# driver.net
KiCad netlist of a schematic drawn in Altium Designer
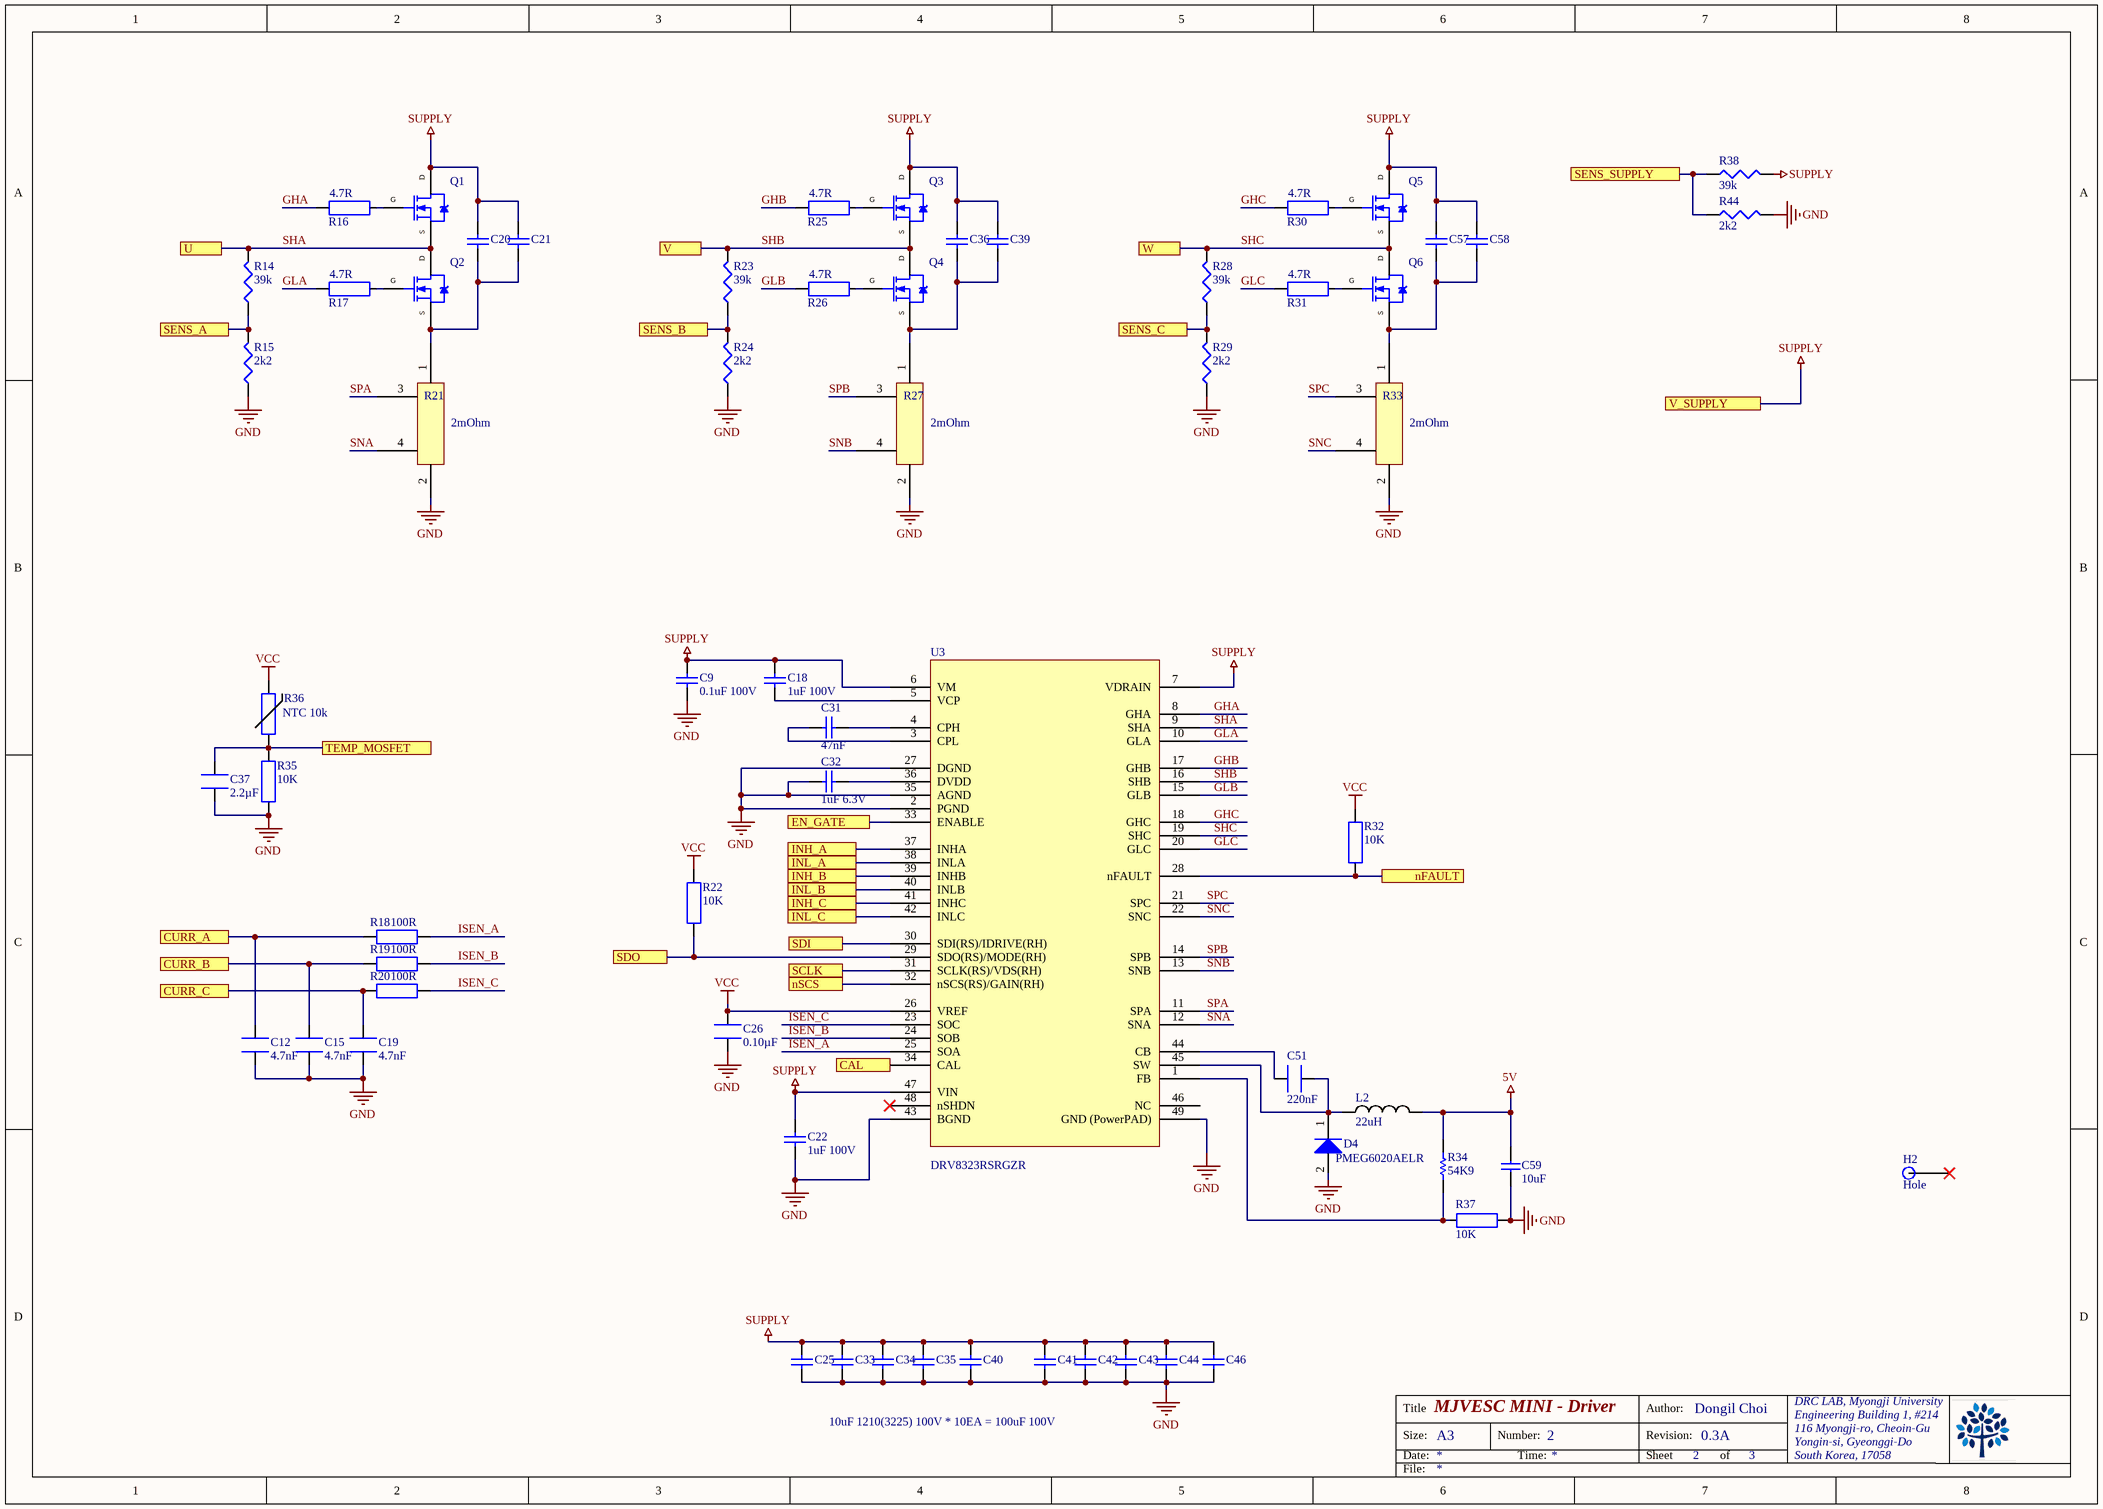
[diagram p0: driver.SchDoc]

(export (version "E")
  (design (tool "Eeschema 10.0.6"))
  (components
    (comp (ref "C9")
      (value "0.1uF 100V")
      (footprint "CAP 0603/1608")
      (description "Multilayer Ceramic Capacitors MLCC - SMD/SMT 0603 0.1uF 100volts X7R 10%")
      (fields (field (name "MANUFACTURER") "Murata") (field (name "PARTNUMBER") "GCJ188R72A104KA01D"))
      (libsource (lib "Altium_CDI_Library_Combined") (part "CAP"))
    )
    (comp (ref "C12")
      (value "4.7nF")
      (footprint "CAP 0603/1608")
      (description "CAP CER 4.7nF 50V NP0 0603")
      (fields (field (name "PARTNUMBER") "GRM1887U1H472JA01D"))
      (libsource (lib "CustomComponents") (part "GRM1885C1H222JA01D"))
    )
    (comp (ref "C15")
      (value "4.7nF")
      (footprint "CAP 0603/1608")
      (description "CAP CER 4.7nF 50V NP0 0603")
      (fields (field (name "PARTNUMBER") "GRM1887U1H472JA01D"))
      (libsource (lib "CustomComponents") (part "GRM1885C1H222JA01D"))
    )
    (comp (ref "C18")
      (value "1uF 100V")
      (footprint "C0805")
      (description "Multilayer Ceramic Capacitors MLCC - SMD/SMT 1.0UF 100V 10% 0805")
      (fields (field (name "MANUFACTURER") "Murata") (field (name "PARTNUMBER") "GRM21BC72A105KE01L"))
      (libsource (lib "Altium_CDI_Library_Combined") (part "CAP"))
    )
    (comp (ref "C19")
      (value "4.7nF")
      (footprint "CAP 0603/1608")
      (description "CAP CER 4.7nF 50V NP0 0603")
      (fields (field (name "PARTNUMBER") "GRM1887U1H472JA01D"))
      (libsource (lib "CustomComponents") (part "GRM1885C1H222JA01D"))
    )
    (comp (ref "C20")
      (value "CAP 10uF 100V 1210(3225)")
      (footprint "CAPC1210(3225)280_N")
      (description "100Vdc 10uF 10% 1210/2502")
      (fields (field (name "TOLERANCE") "Â±20%") (field (name "PARTNUMBER") "GRM32EC72A106KE05L"))
      (libsource (lib "Altium Content Vault") (part "CAP"))
    )
    (comp (ref "C21")
      (value "CAP 10uF 100V 1210(3225)")
      (footprint "CAPC1210(3225)280_N")
      (description "100Vdc 10uF 10% 1210/2502")
      (fields (field (name "TOLERANCE") "Â±20%") (field (name "PARTNUMBER") "GRM32EC72A106KE05L"))
      (libsource (lib "Altium Content Vault") (part "CAP"))
    )
    (comp (ref "C22")
      (value "1uF 100V")
      (footprint "C0805")
      (description "Multilayer Ceramic Capacitors MLCC - SMD/SMT 1.0UF 100V 10% 0805")
      (fields (field (name "MANUFACTURER") "Murata") (field (name "PART NUMBER") "GRM21BC72A105KE01L"))
      (libsource (lib "Altium_CDI_Library_Combined") (part "CAP"))
    )
    (comp (ref "C25")
      (value "CAP 10uF 100V 1210(3225)")
      (footprint "CAPC1210(3225)280_N")
      (description "100Vdc 10uF 10% 1210/2502")
      (fields (field (name "TOLERANCE") "Â±20%") (field (name "PARTNUMBER") "GRM32EC72A106KE05L"))
      (libsource (lib "Altium Content Vault") (part "CAP"))
    )
    (comp (ref "C26")
      (value "0.10µF")
      (footprint "CAP 0603/1608")
      (description "CAP CER 0.1UF 25V X7R 0603")
      (fields
        (field (name "MANUFACTURER") "Murata Electronics North America")
        (field (name "MANUFACTURER PART NUMBER") "GRM188R71E104KA01D")
      )
      (libsource (lib "CustomComponents") (part "GRM188R71E104KA01D"))
    )
    (comp (ref "C31")
      (value "47nF")
      (footprint "CAPC0603(1608)100_L")
      (description "CAP 47nF 16V ±5% 0603 (1608 Metric) Thickness 1mm SMD")
      (fields (field (name "TOLERANCE") "Â±10%") (field (name "PARTNUMBER") "CC0603KRX7R7BB473"))
      (libsource (lib "Altium Content Vault") (part "CAP"))
    )
    (comp (ref "C32")
      (value "1uF 6.3V")
      (footprint "CAPC0603(1608)100_N")
      (description "CAP 1uF 6.3V ±10% 0603 (1608 Metric) Thickness 1mm SMD")
      (fields (field (name "TOLERANCE") "Â±10%") (field (name "PARTNUMBER") "CC0603KRX7R5BB105"))
      (libsource (lib "Altium Content Vault") (part "CAP"))
    )
    (comp (ref "C33")
      (value "CAP 10uF 100V 1210(3225)")
      (footprint "CAPC1210(3225)280_N")
      (description "100Vdc 10uF 10% 1210/2502")
      (fields (field (name "TOLERANCE") "Â±20%") (field (name "PARTNUMBER") "GRM32EC72A106KE05L"))
      (libsource (lib "Altium Content Vault") (part "CAP"))
    )
    (comp (ref "C34")
      (value "CAP 10uF 100V 1210(3225)")
      (footprint "CAPC1210(3225)280_N")
      (description "100Vdc 10uF 10% 1210/2502")
      (fields (field (name "TOLERANCE") "Â±20%") (field (name "PARTNUMBER") "GRM32EC72A106KE05L"))
      (libsource (lib "Altium Content Vault") (part "CAP"))
    )
    (comp (ref "C35")
      (value "CAP 10uF 100V 1210(3225)")
      (footprint "CAPC1210(3225)280_N")
      (description "100Vdc 10uF 10% 1210/2502")
      (fields (field (name "TOLERANCE") "Â±20%") (field (name "PARTNUMBER") "GRM32EC72A106KE05L"))
      (libsource (lib "Altium Content Vault") (part "CAP"))
    )
    (comp (ref "C36")
      (value "CAP 10uF 100V 1210(3225)")
      (footprint "CAPC1210(3225)280_N")
      (description "100Vdc 10uF 10% 1210/2502")
      (fields (field (name "TOLERANCE") "Â±20%") (field (name "PARTNUMBER") "GRM32EC72A106KE05L"))
      (libsource (lib "Altium Content Vault") (part "CAP"))
    )
    (comp (ref "C37")
      (value "2.2µF")
      (footprint "CAP 0603/1608")
      (description "CAP CER 2.2UF 16V X5R 0603")
      (fields
        (field (name "MANUFACTURER") "Murata Electronics North America")
        (field (name "MANUFACTURER PART NUMBER") "GRM188R61C225KE15D")
      )
      (libsource (lib "CustomComponents") (part "GRM188R61C225KE15D"))
    )
    (comp (ref "C39")
      (value "CAP 10uF 100V 1210(3225)")
      (footprint "CAPC1210(3225)280_N")
      (description "100Vdc 10uF 10% 1210/2502")
      (fields (field (name "TOLERANCE") "Â±20%") (field (name "PARTNUMBER") "GRM32EC72A106KE05L"))
      (libsource (lib "Altium Content Vault") (part "CAP"))
    )
    (comp (ref "C40")
      (value "CAP 10uF 100V 1210(3225)")
      (footprint "CAPC1210(3225)280_N")
      (description "100Vdc 10uF 10% 1210/2502")
      (fields (field (name "TOLERANCE") "Â±20%") (field (name "PARTNUMBER") "GRM32EC72A106KE05L"))
      (libsource (lib "Altium Content Vault") (part "CAP"))
    )
    (comp (ref "C41")
      (value "CAP 10uF 100V 1210(3225)")
      (footprint "CAPC1210(3225)280_N")
      (description "100Vdc 10uF 10% 1210/2502")
      (fields (field (name "TOLERANCE") "Â±20%") (field (name "PARTNUMBER") "GRM32EC72A106KE05L"))
      (libsource (lib "Altium Content Vault") (part "CAP"))
    )
    (comp (ref "C42")
      (value "CAP 10uF 100V 1210(3225)")
      (footprint "CAPC1210(3225)280_N")
      (description "100Vdc 10uF 10% 1210/2502")
      (fields (field (name "TOLERANCE") "Â±20%") (field (name "PARTNUMBER") "GRM32EC72A106KE05L"))
      (libsource (lib "Altium Content Vault") (part "CAP"))
    )
    (comp (ref "C43")
      (value "CAP 10uF 100V 1210(3225)")
      (footprint "CAPC1210(3225)280_N")
      (description "100Vdc 10uF 10% 1210/2502")
      (fields (field (name "TOLERANCE") "Â±20%") (field (name "PARTNUMBER") "GRM32EC72A106KE05L"))
      (libsource (lib "Altium Content Vault") (part "CAP"))
    )
    (comp (ref "C44")
      (value "CAP 10uF 100V 1210(3225)")
      (footprint "CAPC1210(3225)280_N")
      (description "100Vdc 10uF 10% 1210/2502")
      (fields (field (name "TOLERANCE") "Â±20%") (field (name "PARTNUMBER") "GRM32EC72A106KE05L"))
      (libsource (lib "Altium Content Vault") (part "CAP"))
    )
    (comp (ref "C46")
      (value "CAP 10uF 100V 1210(3225)")
      (footprint "CAPC1210(3225)280_N")
      (description "100Vdc 10uF 10% 1210/2502")
      (fields (field (name "TOLERANCE") "Â±20%") (field (name "PARTNUMBER") "GRM32EC72A106KE05L"))
      (libsource (lib "Altium Content Vault") (part "CAP"))
    )
    (comp (ref "C51")
      (value "220nF")
      (footprint "CAP 0603/1608")
      (description "CAP CER 220nF 50V X7R 0603")
      (fields (field (name "PARTNUMBER") "GRM188R71H224KAC4J"))
      (libsource (lib "CustomComponents") (part "GRM188R71E104KA01D"))
    )
    (comp (ref "C57")
      (value "CAP 10uF 100V 1210(3225)")
      (footprint "CAPC1210(3225)280_N")
      (description "100Vdc 10uF 10% 1210/2502")
      (fields (field (name "TOLERANCE") "Â±20%") (field (name "PARTNUMBER") "GRM32EC72A106KE05L"))
      (libsource (lib "Altium Content Vault") (part "CAP"))
    )
    (comp (ref "C58")
      (value "CAP 10uF 100V 1210(3225)")
      (footprint "CAPC1210(3225)280_N")
      (description "100Vdc 10uF 10% 1210/2502")
      (fields (field (name "TOLERANCE") "Â±20%") (field (name "PARTNUMBER") "GRM32EC72A106KE05L"))
      (libsource (lib "Altium Content Vault") (part "CAP"))
    )
    (comp (ref "C59")
      (value "10uF")
      (footprint "CAPC1206(3216)190_M")
      (description "Multilayer Ceramic Capacitors MLCC - SMD/SMT 16V 10uF 10% 1.60mm X8L AEC-Q200")
      (fields (field (name "PARTNUMBER") "CGA5L1X8L1C106K160AC"))
      (libsource (lib "Altium_CDI_Library_Combined") (part "CGA5L1X8L1C106K160AC"))
    )
    (comp (ref "D4")
      (value "PMEG6020AELR")
      (footprint "SOD123W")
      (description "60 V, 2 A low leakage current Schottky barrier rectifier")
      (libsource (lib "Altium_CDI_Library_Combined") (part "PMEG6020AELR"))
    )
    (comp (ref "H2")
      (value "Hole")
      (footprint "M2-HOLE")
      (description "M2, M2.5, M3 Hole")
      (libsource (lib "Altium_CDI_Library_Combined") (part "Hole"))
    )
    (comp (ref "L2")
      (value "22uH")
      (footprint "74438335220")
      (description "Fixed Inductors WE-MAPI SMD 3015 22uH 0.60A 1040mOhm")
      (fields (field (name "PARTNUMBER") "74438335220"))
      (libsource (lib "Altium_CDI_Library_Combined") (part "74438335220"))
    )
    (comp (ref "Q1")
      (value "NTMFS5C604NLT1G")
      (footprint "DFN500X600X110-5N")
      (description "Power MOSFET\r\n60 V, 1.2 m, 287 A, Single N−Channel")
      (fields (field (name "MANUFACTURER") "International Rectifier"))
      (libsource (lib "Altium_CDI_Library_Combined") (part "NTMFS5C604NLT1G"))
    )
    (comp (ref "Q2")
      (value "NTMFS5C604NLT1G")
      (footprint "DFN500X600X110-5N")
      (description "Power MOSFET\r\n60 V, 1.2 m, 287 A, Single N−Channel")
      (fields (field (name "MANUFACTURER") "International Rectifier"))
      (libsource (lib "Altium_CDI_Library_Combined") (part "NTMFS5C604NLT1G"))
    )
    (comp (ref "Q3")
      (value "NTMFS5C604NLT1G")
      (footprint "DFN500X600X110-5N")
      (description "Power MOSFET\r\n60 V, 1.2 m, 287 A, Single N−Channel")
      (fields (field (name "MANUFACTURER") "International Rectifier"))
      (libsource (lib "Altium_CDI_Library_Combined") (part "NTMFS5C604NLT1G"))
    )
    (comp (ref "Q4")
      (value "NTMFS5C604NLT1G")
      (footprint "DFN500X600X110-5N")
      (description "Power MOSFET\r\n60 V, 1.2 m, 287 A, Single N−Channel")
      (fields (field (name "MANUFACTURER") "International Rectifier"))
      (libsource (lib "Altium_CDI_Library_Combined") (part "NTMFS5C604NLT1G"))
    )
    (comp (ref "Q5")
      (value "NTMFS5C604NLT1G")
      (footprint "DFN500X600X110-5N")
      (description "Power MOSFET\r\n60 V, 1.2 m, 287 A, Single N−Channel")
      (fields (field (name "MANUFACTURER") "International Rectifier"))
      (libsource (lib "Altium_CDI_Library_Combined") (part "NTMFS5C604NLT1G"))
    )
    (comp (ref "Q6")
      (value "NTMFS5C604NLT1G")
      (footprint "DFN500X600X110-5N")
      (description "Power MOSFET\r\n60 V, 1.2 m, 287 A, Single N−Channel")
      (fields (field (name "MANUFACTURER") "International Rectifier"))
      (libsource (lib "Altium_CDI_Library_Combined") (part "NTMFS5C604NLT1G"))
    )
    (comp (ref "R14")
      (value "39k")
      (footprint "RES 0603/1608")
      (description "RES SMD 39K OHM 1% 1/10W 0603")
      (fields (field (name "PARTNUMBER") "RC0603FR-0739KL") (field (name "PUBLISHER") "Altium Limited"))
      (libsource (lib "Miscellaneous Devices") (part "Res3"))
    )
    (comp (ref "R15")
      (value "2k2")
      (footprint "RES 0603/1608")
      (description "RES SMD 2.2K OHM 1% 1/10W 0603")
      (fields (field (name "PARTNUMBER") "RC0603FR-072K2L") (field (name "PUBLISHER") "Altium Limited"))
      (libsource (lib "Miscellaneous Devices") (part "Res3"))
    )
    (comp (ref "R16")
      (value "4.7R")
      (footprint "RES 0603/1608")
      (description "4.7R 0.1W 1% 0603 (1608 Metric)  SMD")
      (fields (field (name "PARTNUMBER") "RC0603FR-074R7L"))
      (libsource (lib "Altium_CDI_Library_Combined") (part "RC0603FR-072RL"))
    )
    (comp (ref "R17")
      (value "4.7R")
      (footprint "RES 0603/1608")
      (description "4.7R 0.1W 1% 0603 (1608 Metric)  SMD")
      (fields (field (name "PARTNUMBER") "RC0603FR-074R7L"))
      (libsource (lib "Altium_CDI_Library_Combined") (part "RC0603FR-072RL"))
    )
    (comp (ref "R18")
      (value "100R")
      (footprint "RES 0603/1608")
      (description "RES SMD 100R OHM 1% 1/10W 0603")
      (fields (field (name "PARTNUMBER") "RC0603JR-07100RL"))
      (libsource (lib "CustomComponents") (part "RC0603FR-07120RL"))
    )
    (comp (ref "R19")
      (value "100R")
      (footprint "RES 0603/1608")
      (description "RES SMD 100R OHM 1% 1/10W 0603")
      (fields (field (name "PARTNUMBER") "RC0603JR-07100RL"))
      (libsource (lib "CustomComponents") (part "RC0603FR-07120RL"))
    )
    (comp (ref "R20")
      (value "100R")
      (footprint "RES 0603/1608")
      (description "RES SMD 100R OHM 1% 1/10W 0603")
      (fields (field (name "PARTNUMBER") "RC0603JR-07100RL"))
      (libsource (lib "CustomComponents") (part "RC0603FR-07120RL"))
    )
    (comp (ref "R21")
      (value "2mOhm")
      (footprint "CSS2H-2512K-2L00F")
      (description "Current Sense Resistors - SMD 2mOhms 5W 1% AEC-Q200")
      (fields (field (name "PARTNUMBER") "CSS2H-2512K-2L00F"))
      (libsource (lib "Altium_CDI_Library_Combined") (part "CSS2H-2512K-2L00F"))
    )
    (comp (ref "R22")
      (value "10K")
      (footprint "RES 0603/1608")
      (description "RES SMD 10K OHM 1% 1/10W 0603")
      (fields
        (field (name "MANUFACTURER") "Yageo")
        (field (name "MANUFACTURER PART NUMBER") "RC0603FR-0710KL")
      )
      (libsource (lib "CustomComponents") (part "RC0603FR-0710KL"))
    )
    (comp (ref "R23")
      (value "39k")
      (footprint "RES 0603/1608")
      (description "RES SMD 39K OHM 1% 1/10W 0603")
      (fields (field (name "PARTNUMBER") "RC0603FR-0739KL") (field (name "PUBLISHER") "Altium Limited"))
      (libsource (lib "Miscellaneous Devices") (part "Res3"))
    )
    (comp (ref "R24")
      (value "2k2")
      (footprint "RES 0603/1608")
      (description "RES SMD 2.2K OHM 1% 1/10W 0603")
      (fields (field (name "PARTNUMBER") "RC0603FR-072K2L") (field (name "PUBLISHER") "Altium Limited"))
      (libsource (lib "Miscellaneous Devices") (part "Res3"))
    )
    (comp (ref "R25")
      (value "4.7R")
      (footprint "RES 0603/1608")
      (description "4.7R 0.1W 1% 0603 (1608 Metric)  SMD")
      (fields (field (name "PARTNUMBER") "RC0603FR-074R7L"))
      (libsource (lib "Altium_CDI_Library_Combined") (part "RC0603FR-072RL"))
    )
    (comp (ref "R26")
      (value "4.7R")
      (footprint "RES 0603/1608")
      (description "4.7R 0.1W 1% 0603 (1608 Metric)  SMD")
      (fields (field (name "PARTNUMBER") "RC0603FR-074R7L"))
      (libsource (lib "Altium_CDI_Library_Combined") (part "RC0603FR-072RL"))
    )
    (comp (ref "R27")
      (value "2mOhm")
      (footprint "CSS2H-2512K-2L00F")
      (description "Current Sense Resistors - SMD 2mOhms 5W 1% AEC-Q200")
      (fields (field (name "PARTNUMBER") "CSS2H-2512K-2L00F"))
      (libsource (lib "Altium_CDI_Library_Combined") (part "CSS2H-2512K-2L00F"))
    )
    (comp (ref "R28")
      (value "39k")
      (footprint "RES 0603/1608")
      (description "RES SMD 39K OHM 1% 1/10W 0603")
      (fields (field (name "PARTNUMBER") "RC0603FR-0739KL") (field (name "PUBLISHER") "Altium Limited"))
      (libsource (lib "Miscellaneous Devices") (part "Res3"))
    )
    (comp (ref "R29")
      (value "2k2")
      (footprint "RES 0603/1608")
      (description "RES SMD 2.2K OHM 1% 1/10W 0603")
      (fields (field (name "PARTNUMBER") "RC0603FR-072K2L") (field (name "PUBLISHER") "Altium Limited"))
      (libsource (lib "Miscellaneous Devices") (part "Res3"))
    )
    (comp (ref "R30")
      (value "4.7R")
      (footprint "RES 0603/1608")
      (description "4.7R 0.1W 1% 0603 (1608 Metric)  SMD")
      (fields (field (name "PARTNUMBER") "RC0603FR-074R7L"))
      (libsource (lib "Altium_CDI_Library_Combined") (part "RC0603FR-072RL"))
    )
    (comp (ref "R31")
      (value "4.7R")
      (footprint "RES 0603/1608")
      (description "4.7R 0.1W 1% 0603 (1608 Metric)  SMD")
      (fields (field (name "PARTNUMBER") "RC0603FR-074R7L"))
      (libsource (lib "Altium_CDI_Library_Combined") (part "RC0603FR-072RL"))
    )
    (comp (ref "R32")
      (value "10K")
      (footprint "RES 0603/1608")
      (description "RES SMD 10K OHM 1% 1/10W 0603")
      (fields
        (field (name "MANUFACTURER") "Yageo")
        (field (name "MANUFACTURER PART NUMBER") "RC0603FR-0710KL")
      )
      (libsource (lib "CustomComponents") (part "RC0603FR-0710KL"))
    )
    (comp (ref "R33")
      (value "2mOhm")
      (footprint "CSS2H-2512K-2L00F")
      (description "Current Sense Resistors - SMD 2mOhms 5W 1% AEC-Q200")
      (fields (field (name "PARTNUMBER") "CSS2H-2512K-2L00F"))
      (libsource (lib "Altium_CDI_Library_Combined") (part "CSS2H-2512K-2L00F"))
    )
    (comp (ref "R34")
      (value "54K9")
      (footprint "RESC0603(1608)_M")
      (description "54K9 0.1W 1% 0603 (1608 Metric)  SMD")
      (fields (field (name "TOLERANCE") "1 %") (field (name "POWER") "0.1 W"))
      (libsource (lib "Altium Content Vault") (part "RES"))
    )
    (comp (ref "R35")
      (value "10K")
      (footprint "RES 0603/1608")
      (description "RES SMD 10K OHM 1% 1/10W 0603")
      (fields
        (field (name "MANUFACTURER") "Yageo")
        (field (name "MANUFACTURER PART NUMBER") "RC0603FR-0710KL")
      )
      (libsource (lib "CustomComponents") (part "RC0603FR-0710KL"))
    )
    (comp (ref "R36")
      (value "NTC 10k")
      (footprint "RES 0402/1005")
      (description "THERMISTOR 10K OHM NTC 0402 SMD")
      (fields (field (name "PARTNUMBER") "NCP15XH103F03RC"))
      (libsource (lib "CustomComponents") (part "NCP15XH103F03RC"))
    )
    (comp (ref "R37")
      (value "10K")
      (footprint "RES 0603/1608")
      (description "RES SMD 10K OHM 1% 1/10W 0603")
      (fields
        (field (name "MANUFACTURER") "Yageo")
        (field (name "MANUFACTURER PART NUMBER") "RC0603FR-0710KL")
      )
      (libsource (lib "CustomComponents") (part "RC0603FR-0710KL"))
    )
    (comp (ref "R38")
      (value "39k")
      (footprint "RES 0603/1608")
      (description "RES SMD 39K OHM 1% 1/10W 0603")
      (fields (field (name "PARTNUMBER") "RC0603FR-0739KL") (field (name "PUBLISHER") "Altium Limited"))
      (libsource (lib "Miscellaneous Devices") (part "Res3"))
    )
    (comp (ref "R44")
      (value "2k2")
      (footprint "RES 0603/1608")
      (description "RES SMD 2.2K OHM 1% 1/10W 0603")
      (fields (field (name "PARTNUMBER") "RC0603FR-072K2L") (field (name "PUBLISHER") "Altium Limited"))
      (libsource (lib "Miscellaneous Devices") (part "Res3"))
    )
    (comp (ref "U3")
      (value "DRV8323RSRGZR")
      (footprint "VQFN-48_N")
      (fields (field (name "PARTNUMBER") "DRV8323RSRGZR"))
      (libsource (lib "Altium_CDI_Library_Combined") (part "DRV8323RSRGZR"))
    )
  )
  (nets
    (net (code "1") (name "/CAL") (class "Default")
      (node (ref "U3") (pin "34") (pinfunction "CAL_34") (pintype "passive"))
    )
    (net (code "2") (name "/CURR_A") (class "Default")
      (node (ref "C12") (pin "1") (pinfunction "1_1") (pintype "passive"))
      (node (ref "R18") (pin "2") (pinfunction "0_2") (pintype "passive"))
    )
    (net (code "3") (name "/CURR_B") (class "Default")
      (node (ref "C15") (pin "1") (pinfunction "1_1") (pintype "passive"))
      (node (ref "R19") (pin "2") (pinfunction "0_2") (pintype "passive"))
    )
    (net (code "4") (name "/CURR_C") (class "Default")
      (node (ref "C19") (pin "1") (pinfunction "1_1") (pintype "passive"))
      (node (ref "R20") (pin "2") (pinfunction "0_2") (pintype "passive"))
    )
    (net (code "5") (name "/EN_GATE") (class "Default")
      (node (ref "U3") (pin "33") (pinfunction "ENABLE_33") (pintype "passive"))
    )
    (net (code "6") (name "/GHA") (class "Default")
      (node (ref "R16") (pin "1") (pinfunction "0_1") (pintype "passive"))
      (node (ref "U3") (pin "8") (pinfunction "GHA_8") (pintype "passive"))
    )
    (net (code "7") (name "/GHB") (class "Default")
      (node (ref "R25") (pin "1") (pinfunction "0_1") (pintype "passive"))
      (node (ref "U3") (pin "17") (pinfunction "GHB_17") (pintype "passive"))
    )
    (net (code "8") (name "/GHC") (class "Default")
      (node (ref "R30") (pin "1") (pinfunction "0_1") (pintype "passive"))
      (node (ref "U3") (pin "18") (pinfunction "GHC_18") (pintype "passive"))
    )
    (net (code "9") (name "/GLA") (class "Default")
      (node (ref "R17") (pin "1") (pinfunction "0_1") (pintype "passive"))
      (node (ref "U3") (pin "10") (pinfunction "GLA_10") (pintype "passive"))
    )
    (net (code "10") (name "/GLB") (class "Default")
      (node (ref "R26") (pin "1") (pinfunction "0_1") (pintype "passive"))
      (node (ref "U3") (pin "15") (pinfunction "GLB_15") (pintype "passive"))
    )
    (net (code "11") (name "/GLC") (class "Default")
      (node (ref "R31") (pin "1") (pinfunction "0_1") (pintype "passive"))
      (node (ref "U3") (pin "20") (pinfunction "GLC_20") (pintype "passive"))
    )
    (net (code "12") (name "/INH_A") (class "Default")
      (node (ref "U3") (pin "37") (pinfunction "INHA_37") (pintype "passive"))
    )
    (net (code "13") (name "/INH_B") (class "Default")
      (node (ref "U3") (pin "39") (pinfunction "INHB_39") (pintype "passive"))
    )
    (net (code "14") (name "/INH_C") (class "Default")
      (node (ref "U3") (pin "41") (pinfunction "INHC_41") (pintype "passive"))
    )
    (net (code "15") (name "/INL_A") (class "Default")
      (node (ref "U3") (pin "38") (pinfunction "INLA_38") (pintype "passive"))
    )
    (net (code "16") (name "/INL_B") (class "Default")
      (node (ref "U3") (pin "40") (pinfunction "INLB_40") (pintype "passive"))
    )
    (net (code "17") (name "/INL_C") (class "Default")
      (node (ref "U3") (pin "42") (pinfunction "INLC_42") (pintype "passive"))
    )
    (net (code "18") (name "/ISEN_A") (class "Default")
      (node (ref "R18") (pin "1") (pinfunction "0_1") (pintype "passive"))
      (node (ref "U3") (pin "25") (pinfunction "SOA_25") (pintype "passive"))
    )
    (net (code "19") (name "/ISEN_B") (class "Default")
      (node (ref "R19") (pin "1") (pinfunction "0_1") (pintype "passive"))
      (node (ref "U3") (pin "24") (pinfunction "SOB_24") (pintype "passive"))
    )
    (net (code "20") (name "/ISEN_C") (class "Default")
      (node (ref "R20") (pin "1") (pinfunction "0_1") (pintype "passive"))
      (node (ref "U3") (pin "23") (pinfunction "SOC_23") (pintype "passive"))
    )
    (net (code "21") (name "/SCLK") (class "Default")
      (node (ref "U3") (pin "31") (pinfunction "SCLK(RS)/VDS(RH)_31") (pintype "passive"))
    )
    (net (code "22") (name "/SDI") (class "Default")
      (node (ref "U3") (pin "30") (pinfunction "SDI(RS)/IDRIVE(RH)_30") (pintype "passive"))
    )
    (net (code "23") (name "/SDO") (class "Default")
      (node (ref "R22") (pin "2") (pinfunction "0_2") (pintype "passive"))
      (node (ref "U3") (pin "29") (pinfunction "SDO(RS)/MODE(RH)_29") (pintype "passive"))
    )
    (net (code "24") (name "/SENS_A") (class "Default")
      (node (ref "R14") (pin "1") (pinfunction "1_1") (pintype "passive"))
      (node (ref "R15") (pin "2") (pinfunction "2_2") (pintype "passive"))
    )
    (net (code "25") (name "/SENS_B") (class "Default")
      (node (ref "R23") (pin "1") (pinfunction "1_1") (pintype "passive"))
      (node (ref "R24") (pin "2") (pinfunction "2_2") (pintype "passive"))
    )
    (net (code "26") (name "/SENS_C") (class "Default")
      (node (ref "R28") (pin "1") (pinfunction "1_1") (pintype "passive"))
      (node (ref "R29") (pin "2") (pinfunction "2_2") (pintype "passive"))
    )
    (net (code "27") (name "/SENS_SUPPLY") (class "Default")
      (node (ref "R38") (pin "1") (pinfunction "1_1") (pintype "passive"))
      (node (ref "R44") (pin "1") (pinfunction "1_1") (pintype "passive"))
    )
    (net (code "28") (name "/SHA") (class "Default")
      (node (ref "Q1") (pin "1") (pinfunction "S_1") (pintype "passive"))
      (node (ref "Q1") (pin "2") (pinfunction "S_2") (pintype "passive"))
      (node (ref "Q1") (pin "3") (pinfunction "S_3") (pintype "passive"))
      (node (ref "Q2") (pin "5_6") (pinfunction "D_5_6") (pintype "passive"))
      (node (ref "Q2") (pin "5_6_1") (pinfunction "D_5_6_1") (pintype "passive"))
      (node (ref "Q2") (pin "5_6_2") (pinfunction "D_5_6_2") (pintype "passive"))
      (node (ref "Q2") (pin "5_6_3") (pinfunction "D_5_6_3") (pintype "passive"))
      (node (ref "Q2") (pin "5_6_4") (pinfunction "D_5_6_4") (pintype "passive"))
      (node (ref "R14") (pin "2") (pinfunction "2_2") (pintype "passive"))
      (node (ref "U3") (pin "9") (pinfunction "SHA_9") (pintype "passive"))
    )
    (net (code "29") (name "/SHB") (class "Default")
      (node (ref "Q3") (pin "1") (pinfunction "S_1") (pintype "passive"))
      (node (ref "Q3") (pin "2") (pinfunction "S_2") (pintype "passive"))
      (node (ref "Q3") (pin "3") (pinfunction "S_3") (pintype "passive"))
      (node (ref "Q4") (pin "5_6") (pinfunction "D_5_6") (pintype "passive"))
      (node (ref "Q4") (pin "5_6_1") (pinfunction "D_5_6_1") (pintype "passive"))
      (node (ref "Q4") (pin "5_6_2") (pinfunction "D_5_6_2") (pintype "passive"))
      (node (ref "Q4") (pin "5_6_3") (pinfunction "D_5_6_3") (pintype "passive"))
      (node (ref "Q4") (pin "5_6_4") (pinfunction "D_5_6_4") (pintype "passive"))
      (node (ref "R23") (pin "2") (pinfunction "2_2") (pintype "passive"))
      (node (ref "U3") (pin "16") (pinfunction "SHB_16") (pintype "passive"))
    )
    (net (code "30") (name "/SHC") (class "Default")
      (node (ref "Q5") (pin "1") (pinfunction "S_1") (pintype "passive"))
      (node (ref "Q5") (pin "2") (pinfunction "S_2") (pintype "passive"))
      (node (ref "Q5") (pin "3") (pinfunction "S_3") (pintype "passive"))
      (node (ref "Q6") (pin "5_6") (pinfunction "D_5_6") (pintype "passive"))
      (node (ref "Q6") (pin "5_6_1") (pinfunction "D_5_6_1") (pintype "passive"))
      (node (ref "Q6") (pin "5_6_2") (pinfunction "D_5_6_2") (pintype "passive"))
      (node (ref "Q6") (pin "5_6_3") (pinfunction "D_5_6_3") (pintype "passive"))
      (node (ref "Q6") (pin "5_6_4") (pinfunction "D_5_6_4") (pintype "passive"))
      (node (ref "R28") (pin "2") (pinfunction "2_2") (pintype "passive"))
      (node (ref "U3") (pin "19") (pinfunction "SHC_19") (pintype "passive"))
    )
    (net (code "31") (name "/SNA") (class "Default")
      (node (ref "R21") (pin "4") (pinfunction "4_4") (pintype "passive"))
      (node (ref "U3") (pin "12") (pinfunction "SNA_12") (pintype "passive"))
    )
    (net (code "32") (name "/SNB") (class "Default")
      (node (ref "R27") (pin "4") (pinfunction "4_4") (pintype "passive"))
      (node (ref "U3") (pin "13") (pinfunction "SNB_13") (pintype "passive"))
    )
    (net (code "33") (name "/SNC") (class "Default")
      (node (ref "R33") (pin "4") (pinfunction "4_4") (pintype "passive"))
      (node (ref "U3") (pin "22") (pinfunction "SNC_22") (pintype "passive"))
    )
    (net (code "34") (name "/SPA") (class "Default")
      (node (ref "R21") (pin "3") (pinfunction "3_3") (pintype "passive"))
      (node (ref "U3") (pin "11") (pinfunction "SPA_11") (pintype "passive"))
    )
    (net (code "35") (name "/SPB") (class "Default")
      (node (ref "R27") (pin "3") (pinfunction "3_3") (pintype "passive"))
      (node (ref "U3") (pin "14") (pinfunction "SPB_14") (pintype "passive"))
    )
    (net (code "36") (name "/SPC") (class "Default")
      (node (ref "R33") (pin "3") (pinfunction "3_3") (pintype "passive"))
      (node (ref "U3") (pin "21") (pinfunction "SPC_21") (pintype "passive"))
    )
    (net (code "37") (name "/TEMP_MOSFET") (class "Default")
      (node (ref "C37") (pin "2") (pinfunction "2_2") (pintype "passive"))
      (node (ref "R35") (pin "1") (pinfunction "0_1") (pintype "passive"))
      (node (ref "R36") (pin "1") (pinfunction "0_1") (pintype "passive"))
    )
    (net (code "38") (name "/nFAULT") (class "Default")
      (node (ref "R32") (pin "2") (pinfunction "0_2") (pintype "passive"))
      (node (ref "U3") (pin "28") (pinfunction "nFAULT_28") (pintype "passive"))
    )
    (net (code "39") (name "/nSCS") (class "Default")
      (node (ref "U3") (pin "32") (pinfunction "nSCS(RS)/GAIN(RH)_32") (pintype "passive"))
    )
    (net (code "40") (name "5V") (class "Default")
      (node (ref "C59") (pin "2") (pinfunction "2_2") (pintype "passive"))
      (node (ref "L2") (pin "2") (pinfunction "2_2") (pintype "passive"))
      (node (ref "R34") (pin "2") (pinfunction "2_2") (pintype "passive"))
    )
    (net (code "41") (name "GND") (class "Default")
      (node (ref "C12") (pin "2") (pinfunction "2_2") (pintype "passive"))
      (node (ref "C15") (pin "2") (pinfunction "2_2") (pintype "passive"))
      (node (ref "C19") (pin "2") (pinfunction "2_2") (pintype "passive"))
      (node (ref "C22") (pin "1") (pinfunction "1_1") (pintype "passive"))
      (node (ref "C25") (pin "2") (pinfunction "2_2") (pintype "passive"))
      (node (ref "C26") (pin "2") (pinfunction "2_2") (pintype "passive"))
      (node (ref "C32") (pin "1") (pinfunction "1_1") (pintype "passive"))
      (node (ref "C33") (pin "2") (pinfunction "2_2") (pintype "passive"))
      (node (ref "C34") (pin "2") (pinfunction "2_2") (pintype "passive"))
      (node (ref "C35") (pin "2") (pinfunction "2_2") (pintype "passive"))
      (node (ref "C37") (pin "1") (pinfunction "1_1") (pintype "passive"))
      (node (ref "C40") (pin "2") (pinfunction "2_2") (pintype "passive"))
      (node (ref "C41") (pin "2") (pinfunction "2_2") (pintype "passive"))
      (node (ref "C42") (pin "2") (pinfunction "2_2") (pintype "passive"))
      (node (ref "C43") (pin "2") (pinfunction "2_2") (pintype "passive"))
      (node (ref "C44") (pin "2") (pinfunction "2_2") (pintype "passive"))
      (node (ref "C46") (pin "2") (pinfunction "2_2") (pintype "passive"))
      (node (ref "C59") (pin "1") (pinfunction "1_1") (pintype "passive"))
      (node (ref "C9") (pin "1") (pinfunction "1_1") (pintype "passive"))
      (node (ref "D4") (pin "2") (pinfunction "A_2") (pintype "passive"))
      (node (ref "R15") (pin "1") (pinfunction "1_1") (pintype "passive"))
      (node (ref "R21") (pin "2") (pinfunction "2_2") (pintype "passive"))
      (node (ref "R24") (pin "1") (pinfunction "1_1") (pintype "passive"))
      (node (ref "R27") (pin "2") (pinfunction "2_2") (pintype "passive"))
      (node (ref "R29") (pin "1") (pinfunction "1_1") (pintype "passive"))
      (node (ref "R33") (pin "2") (pinfunction "2_2") (pintype "passive"))
      (node (ref "R35") (pin "2") (pinfunction "0_2") (pintype "passive"))
      (node (ref "R37") (pin "2") (pinfunction "0_2") (pintype "passive"))
      (node (ref "R44") (pin "2") (pinfunction "2_2") (pintype "passive"))
      (node (ref "U3") (pin "2") (pinfunction "PGND_2") (pintype "passive"))
      (node (ref "U3") (pin "27") (pinfunction "DGND_27") (pintype "passive"))
      (node (ref "U3") (pin "35") (pinfunction "AGND_35") (pintype "passive"))
      (node (ref "U3") (pin "43") (pinfunction "BGND_43") (pintype "passive"))
      (node (ref "U3") (pin "49") (pinfunction "GND_(PowerPAD)_49") (pintype "passive"))
    )
    (net (code "42") (name "Net-(C20-Pad2)") (class "Default")
      (node (ref "C20") (pin "2") (pinfunction "2_2") (pintype "passive"))
      (node (ref "C21") (pin "2") (pinfunction "2_2") (pintype "passive"))
      (node (ref "Q2") (pin "1") (pinfunction "S_1") (pintype "passive"))
      (node (ref "Q2") (pin "2") (pinfunction "S_2") (pintype "passive"))
      (node (ref "Q2") (pin "3") (pinfunction "S_3") (pintype "passive"))
      (node (ref "R21") (pin "1") (pinfunction "1_1") (pintype "passive"))
    )
    (net (code "43") (name "Net-(C36-Pad2)") (class "Default")
      (node (ref "C36") (pin "2") (pinfunction "2_2") (pintype "passive"))
      (node (ref "C39") (pin "2") (pinfunction "2_2") (pintype "passive"))
      (node (ref "Q4") (pin "1") (pinfunction "S_1") (pintype "passive"))
      (node (ref "Q4") (pin "2") (pinfunction "S_2") (pintype "passive"))
      (node (ref "Q4") (pin "3") (pinfunction "S_3") (pintype "passive"))
      (node (ref "R27") (pin "1") (pinfunction "1_1") (pintype "passive"))
    )
    (net (code "44") (name "Net-(C57-Pad2)") (class "Default")
      (node (ref "C57") (pin "2") (pinfunction "2_2") (pintype "passive"))
      (node (ref "C58") (pin "2") (pinfunction "2_2") (pintype "passive"))
      (node (ref "Q6") (pin "1") (pinfunction "S_1") (pintype "passive"))
      (node (ref "Q6") (pin "2") (pinfunction "S_2") (pintype "passive"))
      (node (ref "Q6") (pin "3") (pinfunction "S_3") (pintype "passive"))
      (node (ref "R33") (pin "1") (pinfunction "1_1") (pintype "passive"))
    )
    (net (code "45") (name "Net-(D4-K)") (class "Default")
      (node (ref "C51") (pin "1") (pinfunction "1_1") (pintype "passive"))
      (node (ref "D4") (pin "1") (pinfunction "K_1") (pintype "passive"))
      (node (ref "L2") (pin "1") (pinfunction "1_1") (pintype "passive"))
      (node (ref "U3") (pin "45") (pinfunction "SW_45") (pintype "passive"))
    )
    (net (code "46") (name "Net-(Q1-G)") (class "Default")
      (node (ref "Q1") (pin "4") (pinfunction "G_4") (pintype "passive"))
      (node (ref "R16") (pin "2") (pinfunction "0_2") (pintype "passive"))
    )
    (net (code "47") (name "Net-(Q2-G)") (class "Default")
      (node (ref "Q2") (pin "4") (pinfunction "G_4") (pintype "passive"))
      (node (ref "R17") (pin "2") (pinfunction "0_2") (pintype "passive"))
    )
    (net (code "48") (name "Net-(Q3-G)") (class "Default")
      (node (ref "Q3") (pin "4") (pinfunction "G_4") (pintype "passive"))
      (node (ref "R25") (pin "2") (pinfunction "0_2") (pintype "passive"))
    )
    (net (code "49") (name "Net-(Q4-G)") (class "Default")
      (node (ref "Q4") (pin "4") (pinfunction "G_4") (pintype "passive"))
      (node (ref "R26") (pin "2") (pinfunction "0_2") (pintype "passive"))
    )
    (net (code "50") (name "Net-(Q5-G)") (class "Default")
      (node (ref "Q5") (pin "4") (pinfunction "G_4") (pintype "passive"))
      (node (ref "R30") (pin "2") (pinfunction "0_2") (pintype "passive"))
    )
    (net (code "51") (name "Net-(Q6-G)") (class "Default")
      (node (ref "Q6") (pin "4") (pinfunction "G_4") (pintype "passive"))
      (node (ref "R31") (pin "2") (pinfunction "0_2") (pintype "passive"))
    )
    (net (code "52") (name "Net-(U3-CB)") (class "Default")
      (node (ref "C51") (pin "2") (pinfunction "2_2") (pintype "passive"))
      (node (ref "U3") (pin "44") (pinfunction "CB_44") (pintype "passive"))
    )
    (net (code "53") (name "Net-(U3-CPH)") (class "Default")
      (node (ref "C31") (pin "2") (pinfunction "2_2") (pintype "passive"))
      (node (ref "U3") (pin "4") (pinfunction "CPH_4") (pintype "passive"))
    )
    (net (code "54") (name "Net-(U3-CPL)") (class "Default")
      (node (ref "C31") (pin "1") (pinfunction "1_1") (pintype "passive"))
      (node (ref "U3") (pin "3") (pinfunction "CPL_3") (pintype "passive"))
    )
    (net (code "55") (name "Net-(U3-DVDD)") (class "Default")
      (node (ref "C32") (pin "2") (pinfunction "2_2") (pintype "passive"))
      (node (ref "U3") (pin "36") (pinfunction "DVDD_36") (pintype "passive"))
    )
    (net (code "56") (name "Net-(U3-FB)") (class "Default")
      (node (ref "R34") (pin "1") (pinfunction "1_1") (pintype "passive"))
      (node (ref "R37") (pin "1") (pinfunction "0_1") (pintype "passive"))
      (node (ref "U3") (pin "1") (pinfunction "FB_1") (pintype "passive"))
    )
    (net (code "57") (name "Net-(U3-VCP)") (class "Default")
      (node (ref "C18") (pin "1") (pinfunction "1_1") (pintype "passive"))
      (node (ref "U3") (pin "5") (pinfunction "VCP_5") (pintype "passive"))
    )
    (net (code "58") (name "SUPPLY") (class "Default")
      (node (ref "C18") (pin "2") (pinfunction "2_2") (pintype "passive"))
      (node (ref "C20") (pin "1") (pinfunction "1_1") (pintype "passive"))
      (node (ref "C21") (pin "1") (pinfunction "1_1") (pintype "passive"))
      (node (ref "C22") (pin "2") (pinfunction "2_2") (pintype "passive"))
      (node (ref "C25") (pin "1") (pinfunction "1_1") (pintype "passive"))
      (node (ref "C33") (pin "1") (pinfunction "1_1") (pintype "passive"))
      (node (ref "C34") (pin "1") (pinfunction "1_1") (pintype "passive"))
      (node (ref "C35") (pin "1") (pinfunction "1_1") (pintype "passive"))
      (node (ref "C36") (pin "1") (pinfunction "1_1") (pintype "passive"))
      (node (ref "C39") (pin "1") (pinfunction "1_1") (pintype "passive"))
      (node (ref "C40") (pin "1") (pinfunction "1_1") (pintype "passive"))
      (node (ref "C41") (pin "1") (pinfunction "1_1") (pintype "passive"))
      (node (ref "C42") (pin "1") (pinfunction "1_1") (pintype "passive"))
      (node (ref "C43") (pin "1") (pinfunction "1_1") (pintype "passive"))
      (node (ref "C44") (pin "1") (pinfunction "1_1") (pintype "passive"))
      (node (ref "C46") (pin "1") (pinfunction "1_1") (pintype "passive"))
      (node (ref "C57") (pin "1") (pinfunction "1_1") (pintype "passive"))
      (node (ref "C58") (pin "1") (pinfunction "1_1") (pintype "passive"))
      (node (ref "C9") (pin "2") (pinfunction "2_2") (pintype "passive"))
      (node (ref "Q1") (pin "5_6") (pinfunction "D_5_6") (pintype "passive"))
      (node (ref "Q1") (pin "5_6_1") (pinfunction "D_5_6_1") (pintype "passive"))
      (node (ref "Q1") (pin "5_6_2") (pinfunction "D_5_6_2") (pintype "passive"))
      (node (ref "Q1") (pin "5_6_3") (pinfunction "D_5_6_3") (pintype "passive"))
      (node (ref "Q1") (pin "5_6_4") (pinfunction "D_5_6_4") (pintype "passive"))
      (node (ref "Q3") (pin "5_6") (pinfunction "D_5_6") (pintype "passive"))
      (node (ref "Q3") (pin "5_6_1") (pinfunction "D_5_6_1") (pintype "passive"))
      (node (ref "Q3") (pin "5_6_2") (pinfunction "D_5_6_2") (pintype "passive"))
      (node (ref "Q3") (pin "5_6_3") (pinfunction "D_5_6_3") (pintype "passive"))
      (node (ref "Q3") (pin "5_6_4") (pinfunction "D_5_6_4") (pintype "passive"))
      (node (ref "Q5") (pin "5_6") (pinfunction "D_5_6") (pintype "passive"))
      (node (ref "Q5") (pin "5_6_1") (pinfunction "D_5_6_1") (pintype "passive"))
      (node (ref "Q5") (pin "5_6_2") (pinfunction "D_5_6_2") (pintype "passive"))
      (node (ref "Q5") (pin "5_6_3") (pinfunction "D_5_6_3") (pintype "passive"))
      (node (ref "Q5") (pin "5_6_4") (pinfunction "D_5_6_4") (pintype "passive"))
      (node (ref "R38") (pin "2") (pinfunction "2_2") (pintype "passive"))
      (node (ref "U3") (pin "47") (pinfunction "VIN_47") (pintype "passive"))
      (node (ref "U3") (pin "6") (pinfunction "VM_6") (pintype "passive"))
      (node (ref "U3") (pin "7") (pinfunction "VDRAIN_7") (pintype "passive"))
    )
    (net (code "59") (name "VCC") (class "Default")
      (node (ref "C26") (pin "1") (pinfunction "1_1") (pintype "passive"))
      (node (ref "R22") (pin "1") (pinfunction "0_1") (pintype "passive"))
      (node (ref "R32") (pin "1") (pinfunction "0_1") (pintype "passive"))
      (node (ref "R36") (pin "2") (pinfunction "0_2") (pintype "passive"))
      (node (ref "U3") (pin "26") (pinfunction "VREF_26") (pintype "passive"))
    )
    (net (code "60") (name "unconnected-(H2-Pad0)") (class "Default")
      (node (ref "H2") (pin "0") (pinfunction "0_0") (pintype "passive+no_connect"))
    )
    (net (code "61") (name "unconnected-(U3-NC-Pad46)") (class "Default")
      (node (ref "U3") (pin "46") (pinfunction "NC_46") (pintype "passive"))
    )
    (net (code "62") (name "unconnected-(U3-nSHDN-Pad48)") (class "Default")
      (node (ref "U3") (pin "48") (pinfunction "nSHDN_48") (pintype "passive+no_connect"))
    )
  )
)
